# LIC_rack_OV-02.net
KiCad netlist of a schematic drawn in EAGLE
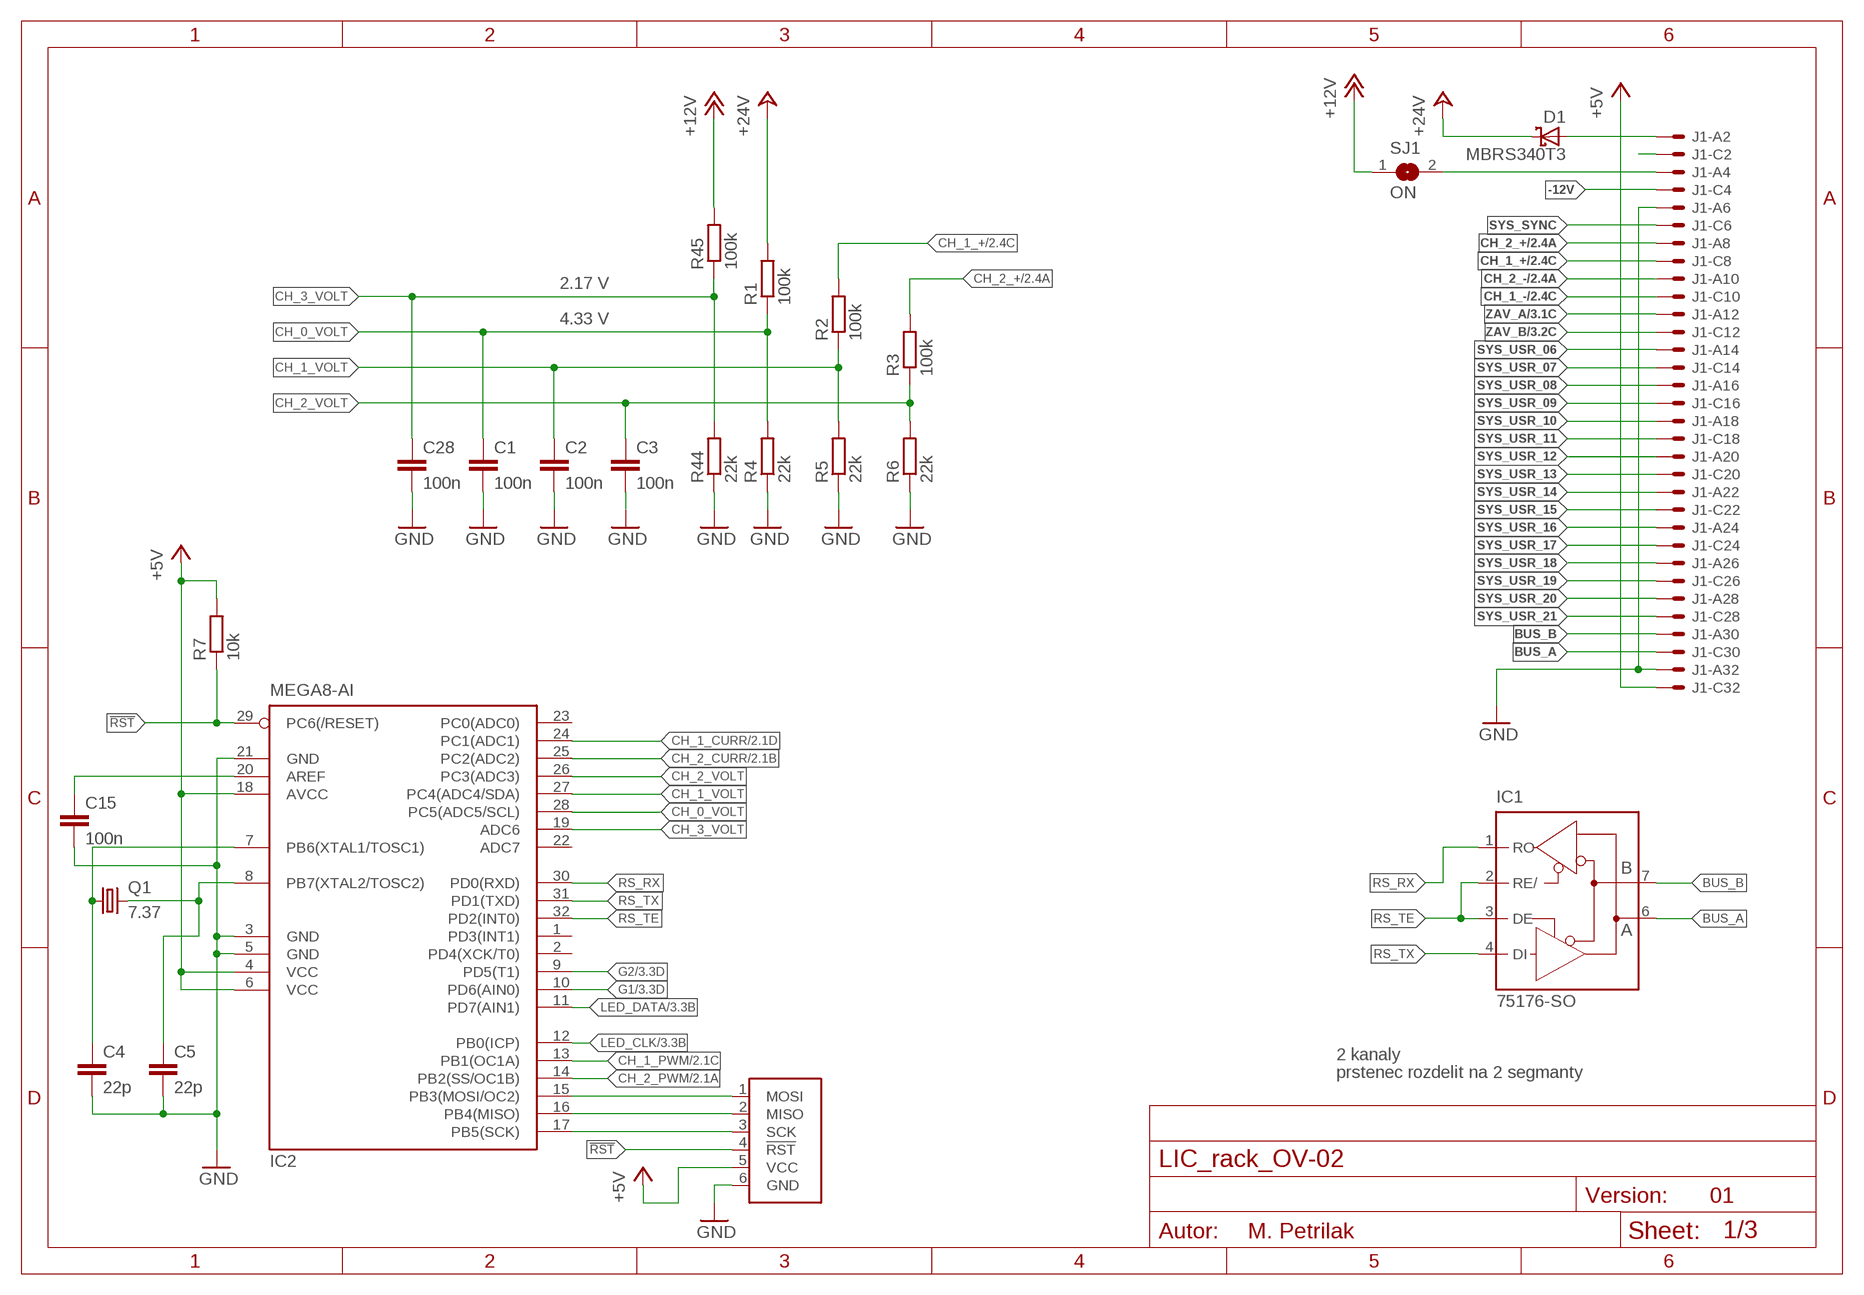
[diagram p0: schematic, sheet 1]
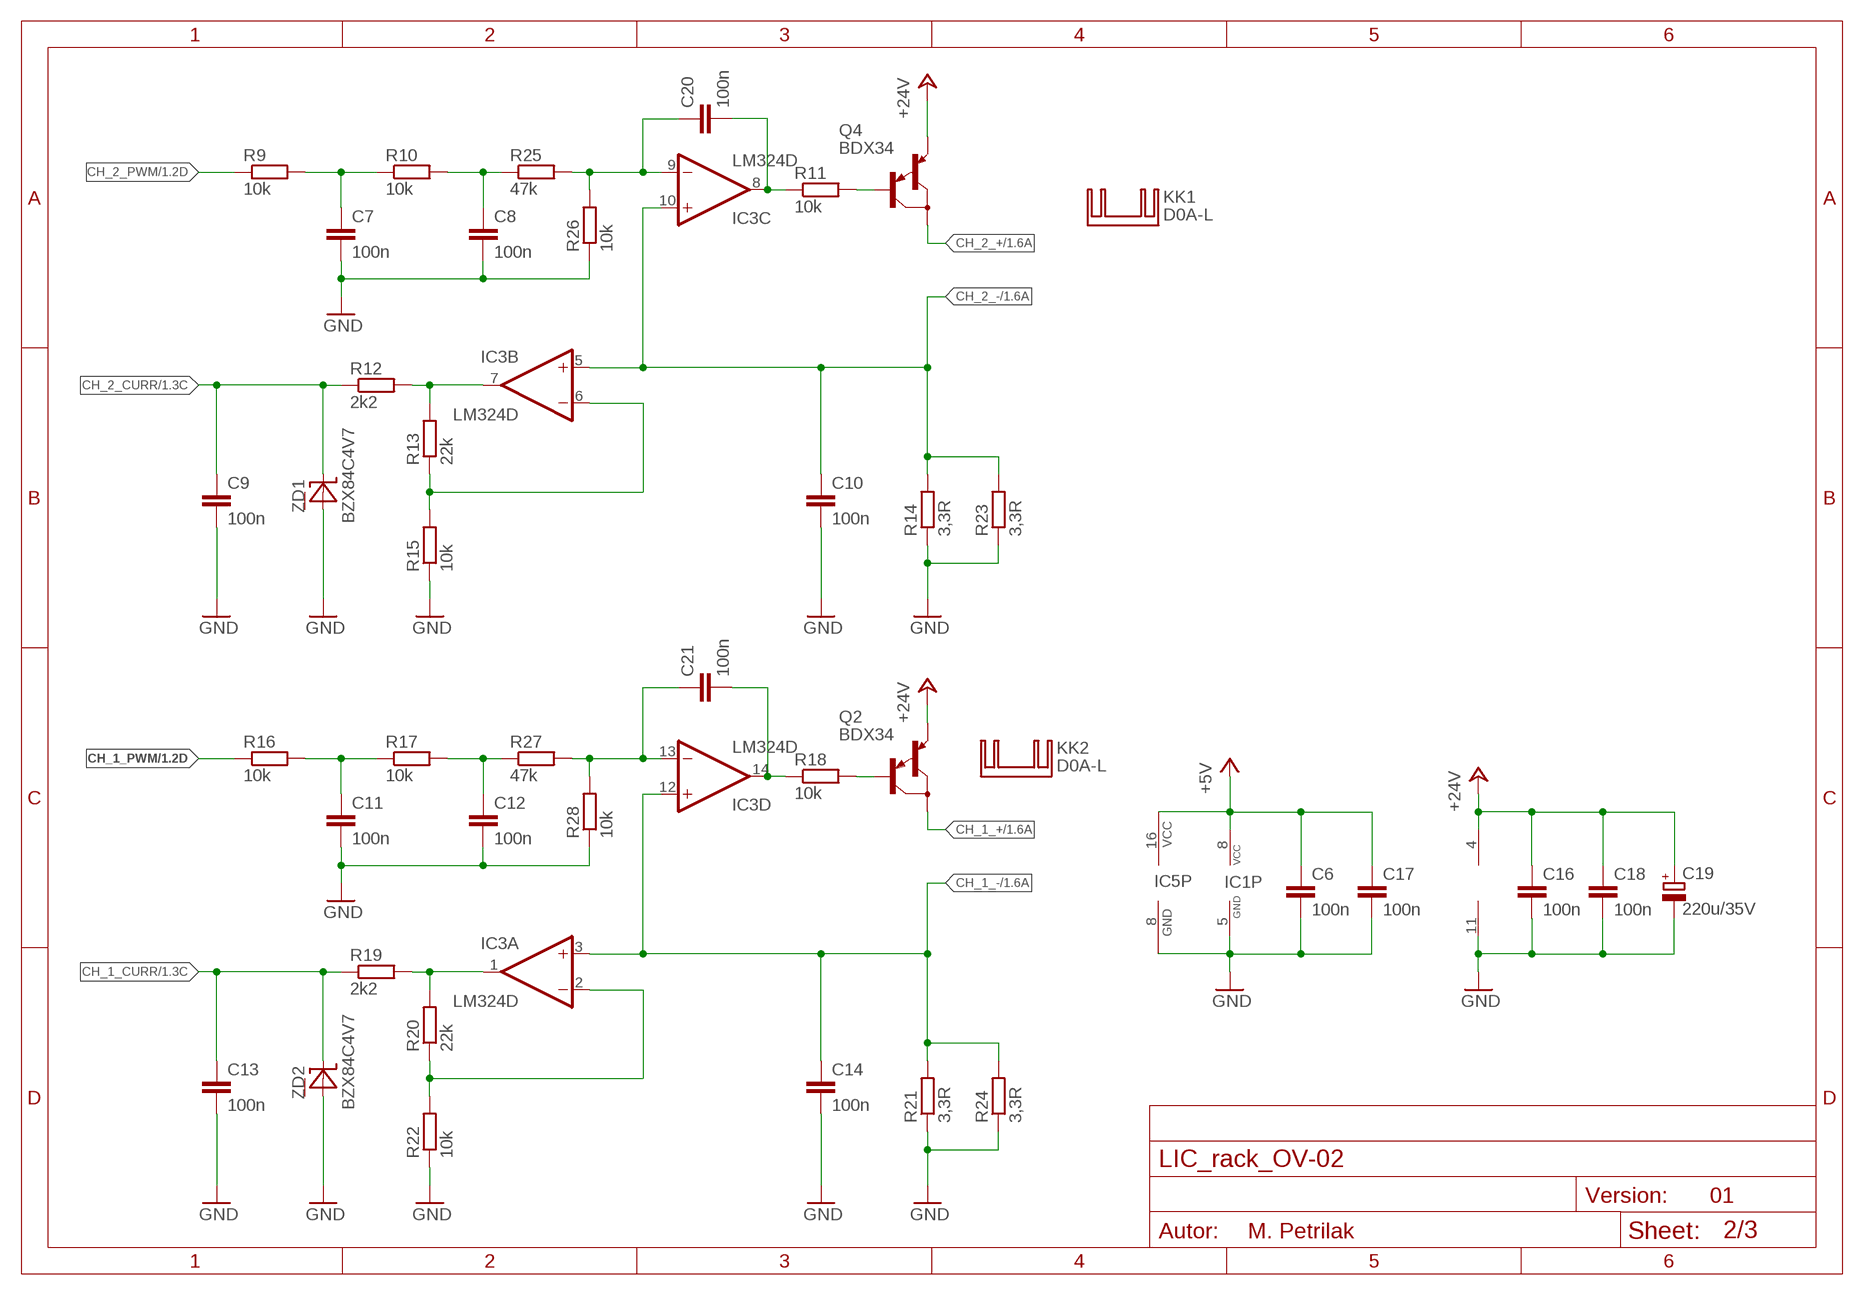
[diagram p1: schematic, sheet 2]
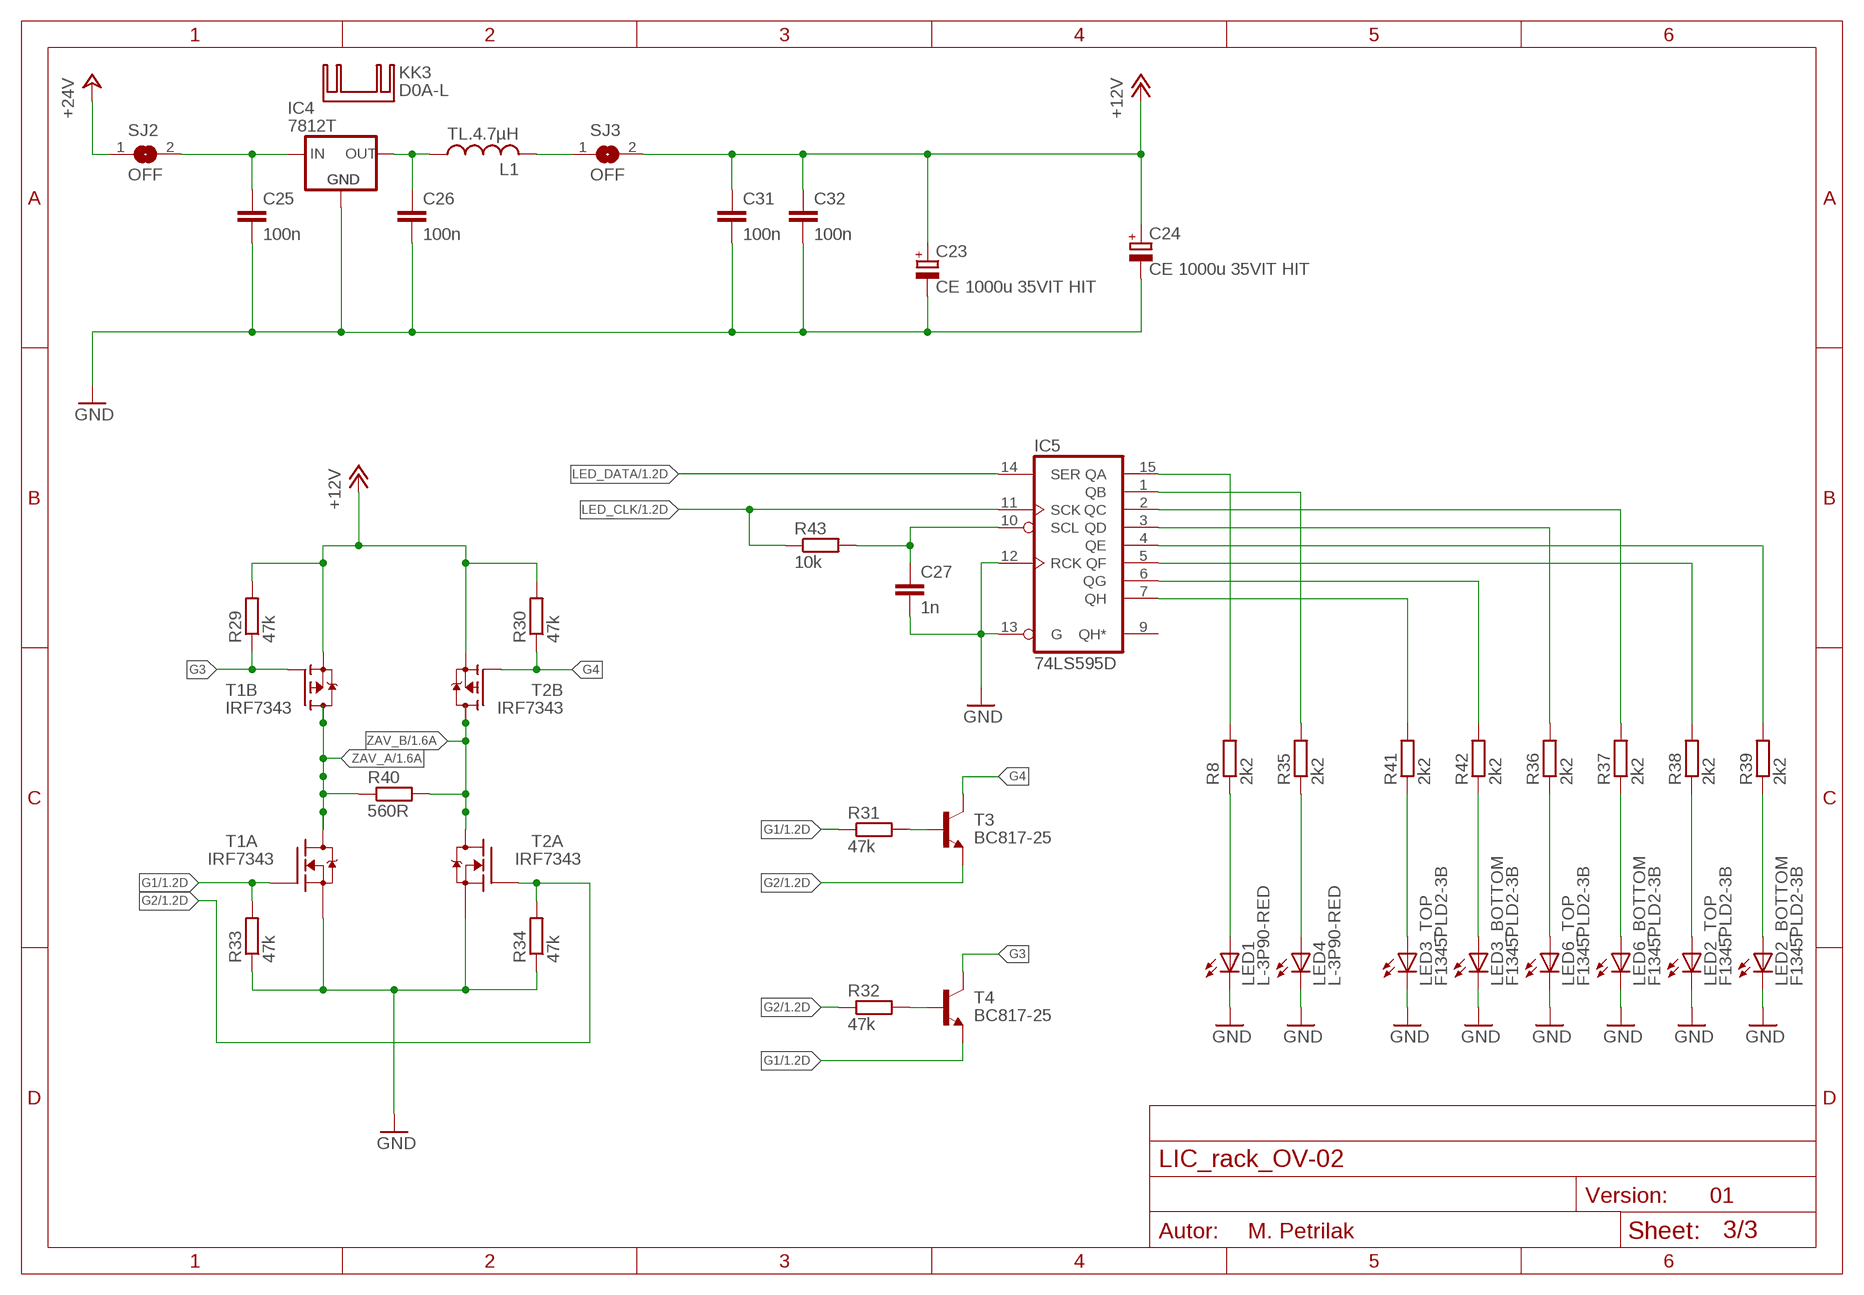
[diagram p2: schematic, sheet 3]

(export (version "E")
  (design (tool "Eeschema 10.0.6"))
  (components
    (comp (ref "C6")
      (value "100n")
      (footprint "eagle-import:C1206")
      (libsource (lib "eagle-import") (part "C-EUC1206"))
    )
    (comp (ref "C7")
      (value "100n")
      (footprint "eagle-import:C1206")
      (libsource (lib "eagle-import") (part "C-EUC1206"))
    )
    (comp (ref "C8")
      (value "100n")
      (footprint "eagle-import:C1206")
      (libsource (lib "eagle-import") (part "C-EUC1206"))
    )
    (comp (ref "C9")
      (value "100n")
      (footprint "eagle-import:C1206")
      (libsource (lib "eagle-import") (part "C-EUC1206"))
    )
    (comp (ref "C10")
      (value "100n")
      (footprint "eagle-import:C1206")
      (libsource (lib "eagle-import") (part "C-EUC1206"))
    )
    (comp (ref "C11")
      (value "100n")
      (footprint "eagle-import:C1206")
      (libsource (lib "eagle-import") (part "C-EUC1206"))
    )
    (comp (ref "C12")
      (value "100n")
      (footprint "eagle-import:C1206")
      (libsource (lib "eagle-import") (part "C-EUC1206"))
    )
    (comp (ref "C13")
      (value "100n")
      (footprint "eagle-import:C1206")
      (libsource (lib "eagle-import") (part "C-EUC1206"))
    )
    (comp (ref "C14")
      (value "100n")
      (footprint "eagle-import:C1206")
      (libsource (lib "eagle-import") (part "C-EUC1206"))
    )
    (comp (ref "C16")
      (value "100n")
      (footprint "eagle-import:C1206")
      (libsource (lib "eagle-import") (part "C-EUC1206"))
    )
    (comp (ref "C17")
      (value "100n")
      (footprint "eagle-import:C1206")
      (libsource (lib "eagle-import") (part "C-EUC1206"))
    )
    (comp (ref "C18")
      (value "100n")
      (footprint "eagle-import:C1206")
      (libsource (lib "eagle-import") (part "C-EUC1206"))
    )
    (comp (ref "C19")
      (value "220u/35V")
      (footprint "eagle-import:E3,5-8LR")
      (libsource (lib "eagle-import") (part "CPOL-EUE3.5-8LR"))
    )
    (comp (ref "C20")
      (value "100n")
      (footprint "eagle-import:C1206")
      (libsource (lib "eagle-import") (part "C-EUC1206"))
    )
    (comp (ref "C21")
      (value "100n")
      (footprint "eagle-import:C1206")
      (libsource (lib "eagle-import") (part "C-EUC1206"))
    )
    (comp (ref "IC1")
      (value "75176-SO")
      (footprint "eagle-import:SO08")
      (libsource (lib "eagle-import") (part "75176-SO"))
    )
    (comp (ref "IC3")
      (value "LM324D")
      (footprint "eagle-import:SO14")
      (libsource (lib "eagle-import") (part "LM324D"))
    )
    (comp (ref "IC5")
      (value "74LS595D")
      (footprint "eagle-import:SO16")
      (libsource (lib "eagle-import") (part "74595DLS"))
    )
    (comp (ref "KK1")
      (value "D0A-L")
      (footprint "eagle-import:D02A-L")
      (libsource (lib "eagle-import") (part "D0A-L"))
    )
    (comp (ref "KK2")
      (value "D0A-L")
      (footprint "eagle-import:D02A-L")
      (libsource (lib "eagle-import") (part "D0A-L"))
    )
    (comp (ref "Q2")
      (value "BDX34")
      (footprint "eagle-import:TO220")
      (libsource (lib "eagle-import") (part "BDX34"))
    )
    (comp (ref "Q4")
      (value "BDX34")
      (footprint "eagle-import:TO220")
      (libsource (lib "eagle-import") (part "BDX34"))
    )
    (comp (ref "R9")
      (value "10k")
      (footprint "eagle-import:R1206")
      (libsource (lib "eagle-import") (part "R-EU_R1206"))
    )
    (comp (ref "R10")
      (value "10k")
      (footprint "eagle-import:R1206")
      (libsource (lib "eagle-import") (part "R-EU_R1206"))
    )
    (comp (ref "R11")
      (value "10k")
      (footprint "eagle-import:R1206")
      (libsource (lib "eagle-import") (part "R-EU_R1206"))
    )
    (comp (ref "R12")
      (value "2k2")
      (footprint "eagle-import:R1206")
      (libsource (lib "eagle-import") (part "R-EU_R1206"))
    )
    (comp (ref "R13")
      (value "22k")
      (footprint "eagle-import:R1206")
      (libsource (lib "eagle-import") (part "R-EU_R1206"))
    )
    (comp (ref "R14")
      (value "3,3R")
      (footprint "eagle-import:0309_12")
      (libsource (lib "eagle-import") (part "R-EU_0309/12"))
    )
    (comp (ref "R15")
      (value "10k")
      (footprint "eagle-import:R1206")
      (libsource (lib "eagle-import") (part "R-EU_R1206"))
    )
    (comp (ref "R16")
      (value "10k")
      (footprint "eagle-import:R1206")
      (libsource (lib "eagle-import") (part "R-EU_R1206"))
    )
    (comp (ref "R17")
      (value "10k")
      (footprint "eagle-import:R1206")
      (libsource (lib "eagle-import") (part "R-EU_R1206"))
    )
    (comp (ref "R18")
      (value "10k")
      (footprint "eagle-import:R1206")
      (libsource (lib "eagle-import") (part "R-EU_R1206"))
    )
    (comp (ref "R19")
      (value "2k2")
      (footprint "eagle-import:R1206")
      (libsource (lib "eagle-import") (part "R-EU_R1206"))
    )
    (comp (ref "R20")
      (value "22k")
      (footprint "eagle-import:R1206")
      (libsource (lib "eagle-import") (part "R-EU_R1206"))
    )
    (comp (ref "R21")
      (value "3,3R")
      (footprint "eagle-import:0309_12")
      (libsource (lib "eagle-import") (part "R-EU_0309/12"))
    )
    (comp (ref "R22")
      (value "10k")
      (footprint "eagle-import:R1206")
      (libsource (lib "eagle-import") (part "R-EU_R1206"))
    )
    (comp (ref "R23")
      (value "3,3R")
      (footprint "eagle-import:R1206")
      (libsource (lib "eagle-import") (part "R-EU_R1206"))
    )
    (comp (ref "R24")
      (value "3,3R")
      (footprint "eagle-import:R1206")
      (libsource (lib "eagle-import") (part "R-EU_R1206"))
    )
    (comp (ref "R25")
      (value "47k")
      (footprint "eagle-import:R1206")
      (libsource (lib "eagle-import") (part "R-EU_R1206"))
    )
    (comp (ref "R26")
      (value "10k")
      (footprint "eagle-import:R1206")
      (libsource (lib "eagle-import") (part "R-EU_R1206"))
    )
    (comp (ref "R27")
      (value "47k")
      (footprint "eagle-import:R1206")
      (libsource (lib "eagle-import") (part "R-EU_R1206"))
    )
    (comp (ref "R28")
      (value "10k")
      (footprint "eagle-import:R1206")
      (libsource (lib "eagle-import") (part "R-EU_R1206"))
    )
    (comp (ref "ZD1")
      (value "BZX84C4V7")
      (footprint "eagle-import:SOT23")
      (libsource (lib "eagle-import") (part "BZX84C4V7"))
    )
    (comp (ref "ZD2")
      (value "BZX84C4V7")
      (footprint "eagle-import:SOT23")
      (libsource (lib "eagle-import") (part "BZX84C4V7"))
    )
    (comp (ref "C1")
      (value "100n")
      (footprint "eagle-import:C1206")
      (libsource (lib "eagle-import") (part "C-EUC1206"))
    )
    (comp (ref "C2")
      (value "100n")
      (footprint "eagle-import:C1206")
      (libsource (lib "eagle-import") (part "C-EUC1206"))
    )
    (comp (ref "C3")
      (value "100n")
      (footprint "eagle-import:C1206")
      (libsource (lib "eagle-import") (part "C-EUC1206"))
    )
    (comp (ref "C4")
      (value "22p")
      (footprint "eagle-import:C0805")
      (libsource (lib "eagle-import") (part "C-EUC0805"))
    )
    (comp (ref "C5")
      (value "22p")
      (footprint "eagle-import:C0805")
      (libsource (lib "eagle-import") (part "C-EUC0805"))
    )
    (comp (ref "C15")
      (value "100n")
      (footprint "eagle-import:C1206")
      (libsource (lib "eagle-import") (part "C-EUC1206"))
    )
    (comp (ref "C28")
      (value "100n")
      (footprint "eagle-import:C1206")
      (libsource (lib "eagle-import") (part "C-EUC1206"))
    )
    (comp (ref "D1")
      (value "MBRS340T3")
      (footprint "eagle-import:SMC")
      (libsource (lib "eagle-import") (part "MBRS340T3"))
    )
    (comp (ref "IC2")
      (value "MEGA8-AI")
      (footprint "eagle-import:TQFP32-08")
      (libsource (lib "eagle-import") (part "MEGA8-AI"))
    )
    (comp (ref "J1")
      (value "VG32SP")
      (footprint "eagle-import:VG32P")
      (libsource (lib "eagle-import") (part "VG32SP"))
    )
    (comp (ref "Q1")
      (value "7.37")
      (footprint "eagle-import:HC49U70")
      (libsource (lib "eagle-import") (part "XTAL"))
    )
    (comp (ref "R1")
      (value "100k")
      (footprint "eagle-import:R1206")
      (libsource (lib "eagle-import") (part "R-EU_R1206"))
    )
    (comp (ref "R2")
      (value "100k")
      (footprint "eagle-import:R1206")
      (libsource (lib "eagle-import") (part "R-EU_R1206"))
    )
    (comp (ref "R3")
      (value "100k")
      (footprint "eagle-import:R1206")
      (libsource (lib "eagle-import") (part "R-EU_R1206"))
    )
    (comp (ref "R4")
      (value "22k")
      (footprint "eagle-import:R1206")
      (libsource (lib "eagle-import") (part "R-EU_R1206"))
    )
    (comp (ref "R5")
      (value "22k")
      (footprint "eagle-import:R1206")
      (libsource (lib "eagle-import") (part "R-EU_R1206"))
    )
    (comp (ref "R6")
      (value "22k")
      (footprint "eagle-import:R1206")
      (libsource (lib "eagle-import") (part "R-EU_R1206"))
    )
    (comp (ref "R7")
      (value "10k")
      (footprint "eagle-import:R1206")
      (libsource (lib "eagle-import") (part "R-EU_R1206"))
    )
    (comp (ref "R44")
      (value "22k")
      (footprint "eagle-import:R1206")
      (libsource (lib "eagle-import") (part "R-EU_R1206"))
    )
    (comp (ref "R45")
      (value "100k")
      (footprint "eagle-import:R1206")
      (libsource (lib "eagle-import") (part "R-EU_R1206"))
    )
    (comp (ref "SJ1")
      (value "ON")
      (footprint "eagle-import:SJ-D")
      (libsource (lib "eagle-import") (part "SJ-DEFAULT"))
    )
    (comp (ref "U1")
      (value "ATPROG-V")
      (footprint "eagle-import:6410-06")
      (libsource (lib "eagle-import") (part "ATPROG-V"))
    )
    (comp (ref "C23")
      (value "CE 1000u 35VIT HIT")
      (footprint "eagle-import:E5-13X26-LR")
      (libsource (lib "eagle-import") (part "CPOL-EUE5-13X26-LR"))
    )
    (comp (ref "C24")
      (value "CE 1000u 35VIT HIT")
      (footprint "eagle-import:E5-13X26-LR")
      (libsource (lib "eagle-import") (part "CPOL-EUE5-13X26-LR"))
    )
    (comp (ref "C25")
      (value "100n")
      (footprint "eagle-import:C1206")
      (libsource (lib "eagle-import") (part "C-EUC1206"))
    )
    (comp (ref "C26")
      (value "100n")
      (footprint "eagle-import:C1206")
      (libsource (lib "eagle-import") (part "C-EUC1206"))
    )
    (comp (ref "C27")
      (value "1n")
      (footprint "eagle-import:C1206")
      (libsource (lib "eagle-import") (part "C-EUC1206"))
    )
    (comp (ref "C31")
      (value "100n")
      (footprint "eagle-import:C1206")
      (libsource (lib "eagle-import") (part "C-EUC1206"))
    )
    (comp (ref "C32")
      (value "100n")
      (footprint "eagle-import:C1206")
      (libsource (lib "eagle-import") (part "C-EUC1206"))
    )
    (comp (ref "IC4")
      (value "7812T")
      (footprint "eagle-import:TO220H")
      (libsource (lib "eagle-import") (part "78T12"))
    )
    (comp (ref "KK3")
      (value "D0A-L")
      (footprint "eagle-import:D02A-L")
      (libsource (lib "eagle-import") (part "D0A-L"))
    )
    (comp (ref "L1")
      (value "TL.4.7µH")
      (footprint "eagle-import:0207_12")
      (libsource (lib "eagle-import") (part "L-EU0207/12"))
    )
    (comp (ref "LED1")
      (value "L-3P90-RED")
      (footprint "eagle-import:L-3P90")
      (libsource (lib "eagle-import") (part "L-3P90-RED"))
    )
    (comp (ref "LED2")
      (value "F1345PLD2-3B")
      (footprint "eagle-import:F1345PLD2-3B")
      (libsource (lib "eagle-import") (part "F1345PLD2-3B"))
    )
    (comp (ref "LED3")
      (value "F1345PLD2-3B")
      (footprint "eagle-import:F1345PLD2-3B")
      (libsource (lib "eagle-import") (part "F1345PLD2-3B"))
    )
    (comp (ref "LED4")
      (value "L-3P90-RED")
      (footprint "eagle-import:L-3P90")
      (libsource (lib "eagle-import") (part "L-3P90-RED"))
    )
    (comp (ref "LED6")
      (value "F1345PLD2-3B")
      (footprint "eagle-import:F1345PLD2-3B")
      (libsource (lib "eagle-import") (part "F1345PLD2-3B"))
    )
    (comp (ref "R8")
      (value "2k2")
      (footprint "eagle-import:R1206")
      (libsource (lib "eagle-import") (part "R-EU_R1206"))
    )
    (comp (ref "R29")
      (value "47k")
      (footprint "eagle-import:R1206")
      (libsource (lib "eagle-import") (part "R-EU_R1206"))
    )
    (comp (ref "R30")
      (value "47k")
      (footprint "eagle-import:R1206")
      (libsource (lib "eagle-import") (part "R-EU_R1206"))
    )
    (comp (ref "R31")
      (value "47k")
      (footprint "eagle-import:R1206")
      (libsource (lib "eagle-import") (part "R-EU_R1206"))
    )
    (comp (ref "R32")
      (value "47k")
      (footprint "eagle-import:R1206")
      (libsource (lib "eagle-import") (part "R-EU_R1206"))
    )
    (comp (ref "R33")
      (value "47k")
      (footprint "eagle-import:R1206")
      (libsource (lib "eagle-import") (part "R-EU_R1206"))
    )
    (comp (ref "R34")
      (value "47k")
      (footprint "eagle-import:R1206")
      (libsource (lib "eagle-import") (part "R-EU_R1206"))
    )
    (comp (ref "R35")
      (value "2k2")
      (footprint "eagle-import:R1206")
      (libsource (lib "eagle-import") (part "R-EU_R1206"))
    )
    (comp (ref "R36")
      (value "2k2")
      (footprint "eagle-import:R1206")
      (libsource (lib "eagle-import") (part "R-EU_R1206"))
    )
    (comp (ref "R37")
      (value "2k2")
      (footprint "eagle-import:R1206")
      (libsource (lib "eagle-import") (part "R-EU_R1206"))
    )
    (comp (ref "R38")
      (value "2k2")
      (footprint "eagle-import:R1206")
      (libsource (lib "eagle-import") (part "R-EU_R1206"))
    )
    (comp (ref "R39")
      (value "2k2")
      (footprint "eagle-import:R1206")
      (libsource (lib "eagle-import") (part "R-EU_R1206"))
    )
    (comp (ref "R40")
      (value "560R")
      (footprint "eagle-import:R1206")
      (libsource (lib "eagle-import") (part "R-EU_R1206"))
    )
    (comp (ref "R41")
      (value "2k2")
      (footprint "eagle-import:R1206")
      (libsource (lib "eagle-import") (part "R-EU_R1206"))
    )
    (comp (ref "R42")
      (value "2k2")
      (footprint "eagle-import:R1206")
      (libsource (lib "eagle-import") (part "R-EU_R1206"))
    )
    (comp (ref "R43")
      (value "10k")
      (footprint "eagle-import:R1206")
      (libsource (lib "eagle-import") (part "R-EU_R1206"))
    )
    (comp (ref "SJ2")
      (value "OFF")
      (footprint "eagle-import:SJ")
      (libsource (lib "eagle-import") (part "SJ"))
    )
    (comp (ref "SJ3")
      (value "OFF")
      (footprint "eagle-import:SJ")
      (libsource (lib "eagle-import") (part "SJ"))
    )
    (comp (ref "T1")
      (value "IRF7343")
      (footprint "eagle-import:SO-8")
      (libsource (lib "eagle-import") (part "IRF7343"))
    )
    (comp (ref "T2")
      (value "IRF7343")
      (footprint "eagle-import:SO-8")
      (libsource (lib "eagle-import") (part "IRF7343"))
    )
    (comp (ref "T3")
      (value "BC817-25")
      (footprint "eagle-import:SOT23-BEC")
      (libsource (lib "eagle-import") (part "-NPN-SOT23-BECBC817-25"))
    )
    (comp (ref "T4")
      (value "BC817-25")
      (footprint "eagle-import:SOT23-BEC")
      (libsource (lib "eagle-import") (part "-NPN-SOT23-BECBC817-25"))
    )
  )
  (nets
    (net (code "1") (name "+5V") (class "Default")
      (node (ref "C17") (pin "1") (pinfunction "1_1") (pintype "passive"))
      (node (ref "C6") (pin "1") (pinfunction "1_1") (pintype "passive"))
      (node (ref "IC1") (pin "8") (pinfunction "VCC_8") (pintype "power_in"))
      (node (ref "IC2") (pin "18") (pinfunction "AVCC_18") (pintype "power_in"))
      (node (ref "IC2") (pin "4") (pinfunction "VCC_4") (pintype "power_in"))
      (node (ref "IC2") (pin "6") (pinfunction "VCC_6") (pintype "power_in"))
      (node (ref "IC5") (pin "16") (pinfunction "VCC_16") (pintype "power_in"))
      (node (ref "J1") (pin "C32") (pinfunction "MSV_C32") (pintype "passive"))
      (node (ref "R7") (pin "2") (pinfunction "2_2") (pintype "passive"))
      (node (ref "U1") (pin "5") (pinfunction "VCC_5") (pintype "power_in"))
    )
    (net (code "2") (name "+12V") (class "Default")
      (node (ref "C23") (pin "+") (pinfunction "+_+") (pintype "passive"))
      (node (ref "C24") (pin "+") (pinfunction "+_+") (pintype "passive"))
      (node (ref "C31") (pin "1") (pinfunction "1_1") (pintype "passive"))
      (node (ref "C32") (pin "1") (pinfunction "1_1") (pintype "passive"))
      (node (ref "R29") (pin "2") (pinfunction "2_2") (pintype "passive"))
      (node (ref "R30") (pin "2") (pinfunction "2_2") (pintype "passive"))
      (node (ref "R45") (pin "2") (pinfunction "2_2") (pintype "passive"))
      (node (ref "SJ1") (pin "1") (pinfunction "1_1") (pintype "passive"))
      (node (ref "SJ3") (pin "2") (pinfunction "2_2") (pintype "passive"))
      (node (ref "T1") (pin "3") (pinfunction "S_3") (pintype "passive"))
      (node (ref "T2") (pin "3") (pinfunction "S_3") (pintype "passive"))
    )
    (net (code "3") (name "+24V") (class "Default")
      (node (ref "C16") (pin "1") (pinfunction "1_1") (pintype "passive"))
      (node (ref "C18") (pin "1") (pinfunction "1_1") (pintype "passive"))
      (node (ref "C19") (pin "+") (pinfunction "+_+") (pintype "passive"))
      (node (ref "D1") (pin "C") (pinfunction "C_C") (pintype "passive"))
      (node (ref "IC3") (pin "4") (pinfunction "V+_4") (pintype "power_in"))
      (node (ref "Q2") (pin "3") (pinfunction "E_3") (pintype "passive"))
      (node (ref "Q4") (pin "3") (pinfunction "E_3") (pintype "passive"))
      (node (ref "R1") (pin "2") (pinfunction "2_2") (pintype "passive"))
      (node (ref "SJ2") (pin "1") (pinfunction "1_1") (pintype "passive"))
    )
    (net (code "4") (name "-12V") (class "Default")
      (node (ref "J1") (pin "C4") (pinfunction "MS_C4") (pintype "passive"))
    )
    (net (code "5") (name "BUS_A") (class "Default")
      (node (ref "IC1") (pin "6") (pinfunction "A_6") (pintype "passive"))
      (node (ref "J1") (pin "C30") (pinfunction "MS_C30") (pintype "passive"))
    )
    (net (code "6") (name "BUS_B") (class "Default")
      (node (ref "IC1") (pin "7") (pinfunction "B_7") (pintype "passive"))
      (node (ref "J1") (pin "A30") (pinfunction "MS_A30") (pintype "passive"))
    )
    (net (code "7") (name "CH_0_VOLT") (class "Default")
      (node (ref "C1") (pin "1") (pinfunction "1_1") (pintype "passive"))
      (node (ref "IC2") (pin "28") (pinfunction "PC5(ADC5/SCL)_28") (pintype "bidirectional"))
      (node (ref "R1") (pin "1") (pinfunction "1_1") (pintype "passive"))
      (node (ref "R4") (pin "2") (pinfunction "2_2") (pintype "passive"))
    )
    (net (code "8") (name "CH_1_+") (class "Default")
      (node (ref "J1") (pin "C8") (pinfunction "MS_C8") (pintype "passive"))
      (node (ref "Q2") (pin "2") (pinfunction "C_2") (pintype "passive"))
      (node (ref "R2") (pin "2") (pinfunction "2_2") (pintype "passive"))
    )
    (net (code "9") (name "CH_1_-") (class "Default")
      (node (ref "C14") (pin "1") (pinfunction "1_1") (pintype "passive"))
      (node (ref "IC3") (pin "12") (pinfunction "+IN_12") (pintype "input"))
      (node (ref "IC3") (pin "3") (pinfunction "+IN_3") (pintype "input"))
      (node (ref "J1") (pin "C10") (pinfunction "MS_C10") (pintype "passive"))
      (node (ref "R21") (pin "2") (pinfunction "2_2") (pintype "passive"))
      (node (ref "R24") (pin "2") (pinfunction "2_2") (pintype "passive"))
    )
    (net (code "10") (name "CH_1_CURR") (class "Default")
      (node (ref "C13") (pin "1") (pinfunction "1_1") (pintype "passive"))
      (node (ref "IC2") (pin "24") (pinfunction "PC1(ADC1)_24") (pintype "bidirectional"))
      (node (ref "R19") (pin "1") (pinfunction "1_1") (pintype "passive"))
      (node (ref "ZD2") (pin "3") (pinfunction "C_3") (pintype "passive"))
    )
    (net (code "11") (name "CH_1_PWM") (class "Default")
      (node (ref "IC2") (pin "13") (pinfunction "PB1(OC1A)_13") (pintype "bidirectional"))
      (node (ref "R16") (pin "1") (pinfunction "1_1") (pintype "passive"))
    )
    (net (code "12") (name "CH_1_VOLT") (class "Default")
      (node (ref "C2") (pin "1") (pinfunction "1_1") (pintype "passive"))
      (node (ref "IC2") (pin "27") (pinfunction "PC4(ADC4/SDA)_27") (pintype "bidirectional"))
      (node (ref "R2") (pin "1") (pinfunction "1_1") (pintype "passive"))
      (node (ref "R5") (pin "2") (pinfunction "2_2") (pintype "passive"))
    )
    (net (code "13") (name "CH_2_+") (class "Default")
      (node (ref "J1") (pin "A8") (pinfunction "MS_A8") (pintype "passive"))
      (node (ref "Q4") (pin "2") (pinfunction "C_2") (pintype "passive"))
      (node (ref "R3") (pin "2") (pinfunction "2_2") (pintype "passive"))
    )
    (net (code "14") (name "CH_2_-") (class "Default")
      (node (ref "C10") (pin "1") (pinfunction "1_1") (pintype "passive"))
      (node (ref "IC3") (pin "10") (pinfunction "+IN_10") (pintype "input"))
      (node (ref "IC3") (pin "5") (pinfunction "+IN_5") (pintype "input"))
      (node (ref "J1") (pin "A10") (pinfunction "MS_A10") (pintype "passive"))
      (node (ref "R14") (pin "2") (pinfunction "2_2") (pintype "passive"))
      (node (ref "R23") (pin "2") (pinfunction "2_2") (pintype "passive"))
    )
    (net (code "15") (name "CH_2_CURR") (class "Default")
      (node (ref "C9") (pin "1") (pinfunction "1_1") (pintype "passive"))
      (node (ref "IC2") (pin "25") (pinfunction "PC2(ADC2)_25") (pintype "bidirectional"))
      (node (ref "R12") (pin "1") (pinfunction "1_1") (pintype "passive"))
      (node (ref "ZD1") (pin "3") (pinfunction "C_3") (pintype "passive"))
    )
    (net (code "16") (name "CH_2_PWM") (class "Default")
      (node (ref "IC2") (pin "14") (pinfunction "PB2(SS/OC1B)_14") (pintype "bidirectional"))
      (node (ref "R9") (pin "1") (pinfunction "1_1") (pintype "passive"))
    )
    (net (code "17") (name "CH_2_VOLT") (class "Default")
      (node (ref "C3") (pin "1") (pinfunction "1_1") (pintype "passive"))
      (node (ref "IC2") (pin "26") (pinfunction "PC3(ADC3)_26") (pintype "bidirectional"))
      (node (ref "R3") (pin "1") (pinfunction "1_1") (pintype "passive"))
      (node (ref "R6") (pin "2") (pinfunction "2_2") (pintype "passive"))
    )
    (net (code "18") (name "CH_3_VOLT") (class "Default")
      (node (ref "C28") (pin "1") (pinfunction "1_1") (pintype "passive"))
      (node (ref "IC2") (pin "19") (pinfunction "ADC6_19") (pintype "bidirectional"))
      (node (ref "R44") (pin "2") (pinfunction "2_2") (pintype "passive"))
      (node (ref "R45") (pin "1") (pinfunction "1_1") (pintype "passive"))
    )
    (net (code "19") (name "G1") (class "Default")
      (node (ref "IC2") (pin "10") (pinfunction "PD6(AIN0)_10") (pintype "bidirectional"))
      (node (ref "R31") (pin "1") (pinfunction "1_1") (pintype "passive"))
      (node (ref "R33") (pin "2") (pinfunction "2_2") (pintype "passive"))
      (node (ref "T1") (pin "2") (pinfunction "G_2") (pintype "passive"))
      (node (ref "T4") (pin "E") (pinfunction "E_E") (pintype "passive"))
    )
    (net (code "20") (name "G2") (class "Default")
      (node (ref "IC2") (pin "9") (pinfunction "PD5(T1)_9") (pintype "bidirectional"))
      (node (ref "R32") (pin "1") (pinfunction "1_1") (pintype "passive"))
      (node (ref "R34") (pin "2") (pinfunction "2_2") (pintype "passive"))
      (node (ref "T2") (pin "2") (pinfunction "G_2") (pintype "passive"))
      (node (ref "T3") (pin "E") (pinfunction "E_E") (pintype "passive"))
    )
    (net (code "21") (name "G3") (class "Default")
      (node (ref "R29") (pin "1") (pinfunction "1_1") (pintype "passive"))
      (node (ref "T1") (pin "4") (pinfunction "G_4") (pintype "passive"))
      (node (ref "T4") (pin "C") (pinfunction "C_C") (pintype "passive"))
    )
    (net (code "22") (name "G4") (class "Default")
      (node (ref "R30") (pin "1") (pinfunction "1_1") (pintype "passive"))
      (node (ref "T2") (pin "4") (pinfunction "G_4") (pintype "passive"))
      (node (ref "T3") (pin "C") (pinfunction "C_C") (pintype "passive"))
    )
    (net (code "23") (name "GND") (class "Default")
      (node (ref "C1") (pin "2") (pinfunction "2_2") (pintype "passive"))
      (node (ref "C10") (pin "2") (pinfunction "2_2") (pintype "passive"))
      (node (ref "C11") (pin "2") (pinfunction "2_2") (pintype "passive"))
      (node (ref "C12") (pin "2") (pinfunction "2_2") (pintype "passive"))
      (node (ref "C13") (pin "2") (pinfunction "2_2") (pintype "passive"))
      (node (ref "C14") (pin "2") (pinfunction "2_2") (pintype "passive"))
      (node (ref "C15") (pin "2") (pinfunction "2_2") (pintype "passive"))
      (node (ref "C16") (pin "2") (pinfunction "2_2") (pintype "passive"))
      (node (ref "C17") (pin "2") (pinfunction "2_2") (pintype "passive"))
      (node (ref "C18") (pin "2") (pinfunction "2_2") (pintype "passive"))
      (node (ref "C19") (pin "-") (pinfunction "-_-") (pintype "passive"))
      (node (ref "C2") (pin "2") (pinfunction "2_2") (pintype "passive"))
      (node (ref "C23") (pin "-") (pinfunction "-_-") (pintype "passive"))
      (node (ref "C24") (pin "-") (pinfunction "-_-") (pintype "passive"))
      (node (ref "C25") (pin "2") (pinfunction "2_2") (pintype "passive"))
      (node (ref "C26") (pin "2") (pinfunction "2_2") (pintype "passive"))
      (node (ref "C27") (pin "2") (pinfunction "2_2") (pintype "passive"))
      (node (ref "C28") (pin "2") (pinfunction "2_2") (pintype "passive"))
      (node (ref "C3") (pin "2") (pinfunction "2_2") (pintype "passive"))
      (node (ref "C31") (pin "2") (pinfunction "2_2") (pintype "passive"))
      (node (ref "C32") (pin "2") (pinfunction "2_2") (pintype "passive"))
      (node (ref "C4") (pin "2") (pinfunction "2_2") (pintype "passive"))
      (node (ref "C5") (pin "2") (pinfunction "2_2") (pintype "passive"))
      (node (ref "C6") (pin "2") (pinfunction "2_2") (pintype "passive"))
      (node (ref "C7") (pin "2") (pinfunction "2_2") (pintype "passive"))
      (node (ref "C8") (pin "2") (pinfunction "2_2") (pintype "passive"))
      (node (ref "C9") (pin "2") (pinfunction "2_2") (pintype "passive"))
      (node (ref "IC1") (pin "5") (pinfunction "GND_5") (pintype "power_in"))
      (node (ref "IC2") (pin "21") (pinfunction "GND_21") (pintype "power_in"))
      (node (ref "IC2") (pin "3") (pinfunction "GND_3") (pintype "power_in"))
      (node (ref "IC2") (pin "5") (pinfunction "GND_5") (pintype "power_in"))
      (node (ref "IC3") (pin "11") (pinfunction "V-_11") (pintype "power_in"))
      (node (ref "IC4") (pin "2") (pinfunction "GND_2") (pintype "passive"))
      (node (ref "IC5") (pin "12") (pinfunction "RCK_12") (pintype "input"))
      (node (ref "IC5") (pin "13") (pinfunction "G_13") (pintype "input"))
      (node (ref "IC5") (pin "8") (pinfunction "GND_8") (pintype "power_in"))
      (node (ref "J1") (pin "A32") (pinfunction "MS_A32") (pintype "passive"))
      (node (ref "J1") (pin "A6") (pinfunction "MS_A6") (pintype "passive"))
      (node (ref "LED1") (pin "K") (pinfunction "C_K") (pintype "passive"))
      (node (ref "LED2") (pin "1K") (pinfunction "C_1K") (pintype "passive"))
      (node (ref "LED2") (pin "2K") (pinfunction "C_2K") (pintype "passive"))
      (node (ref "LED3") (pin "1K") (pinfunction "C_1K") (pintype "passive"))
      (node (ref "LED3") (pin "2K") (pinfunction "C_2K") (pintype "passive"))
      (node (ref "LED4") (pin "K") (pinfunction "C_K") (pintype "passive"))
      (node (ref "LED6") (pin "1K") (pinfunction "C_1K") (pintype "passive"))
      (node (ref "LED6") (pin "2K") (pinfunction "C_2K") (pintype "passive"))
      (node (ref "R14") (pin "1") (pinfunction "1_1") (pintype "passive"))
      (node (ref "R15") (pin "1") (pinfunction "1_1") (pintype "passive"))
      (node (ref "R21") (pin "1") (pinfunction "1_1") (pintype "passive"))
      (node (ref "R22") (pin "1") (pinfunction "1_1") (pintype "passive"))
      (node (ref "R23") (pin "1") (pinfunction "1_1") (pintype "passive"))
      (node (ref "R24") (pin "1") (pinfunction "1_1") (pintype "passive"))
      (node (ref "R26") (pin "1") (pinfunction "1_1") (pintype "passive"))
      (node (ref "R28") (pin "1") (pinfunction "1_1") (pintype "passive"))
      (node (ref "R33") (pin "1") (pinfunction "1_1") (pintype "passive"))
      (node (ref "R34") (pin "1") (pinfunction "1_1") (pintype "passive"))
      (node (ref "R4") (pin "1") (pinfunction "1_1") (pintype "passive"))
      (node (ref "R44") (pin "1") (pinfunction "1_1") (pintype "passive"))
      (node (ref "R5") (pin "1") (pinfunction "1_1") (pintype "passive"))
      (node (ref "R6") (pin "1") (pinfunction "1_1") (pintype "passive"))
      (node (ref "T1") (pin "1") (pinfunction "S_1") (pintype "passive"))
      (node (ref "T2") (pin "1") (pinfunction "S_1") (pintype "passive"))
      (node (ref "U1") (pin "6") (pinfunction "GND_6") (pintype "power_in"))
      (node (ref "ZD1") (pin "1") (pinfunction "A_1") (pintype "passive"))
      (node (ref "ZD2") (pin "1") (pinfunction "A_1") (pintype "passive"))
    )
    (net (code "24") (name "LED_CLK") (class "Default")
      (node (ref "IC2") (pin "12") (pinfunction "PB0(ICP)_12") (pintype "bidirectional"))
      (node (ref "IC5") (pin "11") (pinfunction "SCK_11") (pintype "input"))
      (node (ref "R43") (pin "1") (pinfunction "1_1") (pintype "passive"))
    )
    (net (code "25") (name "LED_DATA") (class "Default")
      (node (ref "IC2") (pin "11") (pinfunction "PD7(AIN1)_11") (pintype "bidirectional"))
      (node (ref "IC5") (pin "14") (pinfunction "SER_14") (pintype "input"))
    )
    (net (code "26") (name "Net-(C7-Pad1)") (class "Default")
      (node (ref "C7") (pin "1") (pinfunction "1_1") (pintype "passive"))
      (node (ref "R10") (pin "1") (pinfunction "1_1") (pintype "passive"))
      (node (ref "R9") (pin "2") (pinfunction "2_2") (pintype "passive"))
    )
    (net (code "27") (name "Net-(C8-Pad1)") (class "Default")
      (node (ref "C8") (pin "1") (pinfunction "1_1") (pintype "passive"))
      (node (ref "R10") (pin "2") (pinfunction "2_2") (pintype "passive"))
      (node (ref "R25") (pin "1") (pinfunction "1_1") (pintype "passive"))
    )
    (net (code "28") (name "Net-(C11-Pad1)") (class "Default")
      (node (ref "C11") (pin "1") (pinfunction "1_1") (pintype "passive"))
      (node (ref "R16") (pin "2") (pinfunction "2_2") (pintype "passive"))
      (node (ref "R17") (pin "1") (pinfunction "1_1") (pintype "passive"))
    )
    (net (code "29") (name "Net-(C12-Pad1)") (class "Default")
      (node (ref "C12") (pin "1") (pinfunction "1_1") (pintype "passive"))
      (node (ref "R17") (pin "2") (pinfunction "2_2") (pintype "passive"))
      (node (ref "R27") (pin "1") (pinfunction "1_1") (pintype "passive"))
    )
    (net (code "30") (name "Net-(IC2-AREF)") (class "Default")
      (node (ref "C15") (pin "1") (pinfunction "1_1") (pintype "passive"))
      (node (ref "IC2") (pin "20") (pinfunction "AREF_20") (pintype "passive"))
    )
    (net (code "31") (name "Net-(IC2-PB3(MOSI{slash}OC2))") (class "Default")
      (node (ref "IC2") (pin "15") (pinfunction "PB3(MOSI/OC2)_15") (pintype "bidirectional"))
      (node (ref "U1") (pin "1") (pinfunction "MOSI_1") (pintype "output"))
    )
    (net (code "32") (name "Net-(IC2-PB4(MISO))") (class "Default")
      (node (ref "IC2") (pin "16") (pinfunction "PB4(MISO)_16") (pintype "bidirectional"))
      (node (ref "U1") (pin "2") (pinfunction "MISO_2") (pintype "input"))
    )
    (net (code "33") (name "Net-(IC2-PB5(SCK))") (class "Default")
      (node (ref "IC2") (pin "17") (pinfunction "PB5(SCK)_17") (pintype "bidirectional"))
      (node (ref "U1") (pin "3") (pinfunction "SCK_3") (pintype "input"))
    )
    (net (code "34") (name "Net-(IC2-PB6(XTAL1{slash}TOSC1))") (class "Default")
      (node (ref "C4") (pin "1") (pinfunction "1_1") (pintype "passive"))
      (node (ref "IC2") (pin "7") (pinfunction "PB6(XTAL1/TOSC1)_7") (pintype "bidirectional"))
      (node (ref "Q1") (pin "1") (pinfunction "1_1") (pintype "passive"))
    )
    (net (code "35") (name "Net-(IC2-PB7(XTAL2{slash}TOSC2))") (class "Default")
      (node (ref "C5") (pin "1") (pinfunction "1_1") (pintype "passive"))
      (node (ref "IC2") (pin "8") (pinfunction "PB7(XTAL2/TOSC2)_8") (pintype "bidirectional"))
      (node (ref "Q1") (pin "2") (pinfunction "2_2") (pintype "passive"))
    )
    (net (code "36") (name "Net-(IC3A--IN)") (class "Default")
      (node (ref "IC3") (pin "2") (pinfunction "-IN_2") (pintype "input"))
      (node (ref "R20") (pin "1") (pinfunction "1_1") (pintype "passive"))
      (node (ref "R22") (pin "2") (pinfunction "2_2") (pintype "passive"))
    )
    (net (code "37") (name "Net-(IC3A-OUT)") (class "Default")
      (node (ref "IC3") (pin "1") (pinfunction "OUT_1") (pintype "output"))
      (node (ref "R19") (pin "2") (pinfunction "2_2") (pintype "passive"))
      (node (ref "R20") (pin "2") (pinfunction "2_2") (pintype "passive"))
    )
    (net (code "38") (name "Net-(IC3B--IN)") (class "Default")
      (node (ref "IC3") (pin "6") (pinfunction "-IN_6") (pintype "input"))
      (node (ref "R13") (pin "1") (pinfunction "1_1") (pintype "passive"))
      (node (ref "R15") (pin "2") (pinfunction "2_2") (pintype "passive"))
    )
    (net (code "39") (name "Net-(IC3B-OUT)") (class "Default")
      (node (ref "IC3") (pin "7") (pinfunction "OUT_7") (pintype "output"))
      (node (ref "R12") (pin "2") (pinfunction "2_2") (pintype "passive"))
      (node (ref "R13") (pin "2") (pinfunction "2_2") (pintype "passive"))
    )
    (net (code "40") (name "Net-(IC3C--IN)") (class "Default")
      (node (ref "C20") (pin "1") (pinfunction "1_1") (pintype "passive"))
      (node (ref "IC3") (pin "9") (pinfunction "-IN_9") (pintype "input"))
      (node (ref "R25") (pin "2") (pinfunction "2_2") (pintype "passive"))
      (node (ref "R26") (pin "2") (pinfunction "2_2") (pintype "passive"))
    )
    (net (code "41") (name "Net-(IC3C-OUT)") (class "Default")
      (node (ref "C20") (pin "2") (pinfunction "2_2") (pintype "passive"))
      (node (ref "IC3") (pin "8") (pinfunction "OUT_8") (pintype "output"))
      (node (ref "R11") (pin "1") (pinfunction "1_1") (pintype "passive"))
    )
    (net (code "42") (name "Net-(IC3D--IN)") (class "Default")
      (node (ref "C21") (pin "1") (pinfunction "1_1") (pintype "passive"))
      (node (ref "IC3") (pin "13") (pinfunction "-IN_13") (pintype "input"))
      (node (ref "R27") (pin "2") (pinfunction "2_2") (pintype "passive"))
      (node (ref "R28") (pin "2") (pinfunction "2_2") (pintype "passive"))
    )
    (net (code "43") (name "Net-(IC3D-OUT)") (class "Default")
      (node (ref "C21") (pin "2") (pinfunction "2_2") (pintype "passive"))
      (node (ref "IC3") (pin "14") (pinfunction "OUT_14") (pintype "output"))
      (node (ref "R18") (pin "1") (pinfunction "1_1") (pintype "passive"))
    )
    (net (code "44") (name "Net-(IC4-VI)") (class "Default")
      (node (ref "C25") (pin "1") (pinfunction "1_1") (pintype "passive"))
      (node (ref "IC4") (pin "1") (pinfunction "VI_1") (pintype "input"))
      (node (ref "SJ2") (pin "2") (pinfunction "2_2") (pintype "passive"))
    )
    (net (code "45") (name "Net-(IC4-VO)") (class "Default")
      (node (ref "C26") (pin "1") (pinfunction "1_1") (pintype "passive"))
      (node (ref "IC4") (pin "3") (pinfunction "VO_3") (pintype "passive"))
      (node (ref "L1") (pin "1") (pinfunction "1_1") (pintype "passive"))
    )
    (net (code "46") (name "Net-(IC5A-QA)") (class "Default")
      (node (ref "IC5") (pin "15") (pinfunction "QA_15") (pintype "tri_state"))
      (node (ref "R8") (pin "2") (pinfunction "2_2") (pintype "passive"))
    )
    (net (code "47") (name "Net-(IC5A-QB)") (class "Default")
      (node (ref "IC5") (pin "1") (pinfunction "QB_1") (pintype "tri_state"))
      (node (ref "R35") (pin "2") (pinfunction "2_2") (pintype "passive"))
    )
    (net (code "48") (name "Net-(IC5A-QC)") (class "Default")
      (node (ref "IC5") (pin "2") (pinfunction "QC_2") (pintype "tri_state"))
      (node (ref "R37") (pin "2") (pinfunction "2_2") (pintype "passive"))
    )
    (net (code "49") (name "Net-(IC5A-QD)") (class "Default")
      (node (ref "IC5") (pin "3") (pinfunction "QD_3") (pintype "tri_state"))
      (node (ref "R36") (pin "2") (pinfunction "2_2") (pintype "passive"))
    )
    (net (code "50") (name "Net-(IC5A-QE)") (class "Default")
      (node (ref "IC5") (pin "4") (pinfunction "QE_4") (pintype "tri_state"))
      (node (ref "R39") (pin "2") (pinfunction "2_2") (pintype "passive"))
    )
    (net (code "51") (name "Net-(IC5A-QF)") (class "Default")
      (node (ref "IC5") (pin "5") (pinfunction "QF_5") (pintype "tri_state"))
      (node (ref "R38") (pin "2") (pinfunction "2_2") (pintype "passive"))
    )
    (net (code "52") (name "Net-(IC5A-QG)") (class "Default")
      (node (ref "IC5") (pin "6") (pinfunction "QG_6") (pintype "tri_state"))
      (node (ref "R42") (pin "2") (pinfunction "2_2") (pintype "passive"))
    )
    (net (code "53") (name "Net-(IC5A-QH)") (class "Default")
      (node (ref "IC5") (pin "7") (pinfunction "QH_7") (pintype "tri_state"))
      (node (ref "R41") (pin "2") (pinfunction "2_2") (pintype "passive"))
    )
    (net (code "54") (name "Net-(IC5A-SCL)") (class "Default")
      (node (ref "C27") (pin "1") (pinfunction "1_1") (pintype "passive"))
      (node (ref "IC5") (pin "10") (pinfunction "SCL_10") (pintype "input"))
      (node (ref "R43") (pin "2") (pinfunction "2_2") (pintype "passive"))
    )
    (net (code "55") (name "Net-(J1F-MS)") (class "Default")
      (node (ref "D1") (pin "A") (pinfunction "A_A") (pintype "passive"))
      (node (ref "J1") (pin "A2") (pinfunction "MS_A2") (pintype "passive"))
    )
    (net (code "56") (name "Net-(J1N-MS)") (class "Default")
      (node (ref "J1") (pin "A4") (pinfunction "MS_A4") (pintype "passive"))
      (node (ref "SJ1") (pin "2") (pinfunction "2_2") (pintype "passive"))
    )
    (net (code "57") (name "Net-(L1-Pad2)") (class "Default")
      (node (ref "L1") (pin "2") (pinfunction "2_2") (pintype "passive"))
      (node (ref "SJ3") (pin "1") (pinfunction "1_1") (pintype "passive"))
    )
    (net (code "58") (name "Net-(LED1-PadA)") (class "Default")
      (node (ref "LED1") (pin "A") (pinfunction "A_A") (pintype "passive"))
      (node (ref "R8") (pin "1") (pinfunction "1_1") (pintype "passive"))
    )
    (net (code "59") (name "Net-(LED2A-A)") (class "Default")
      (node (ref "LED2") (pin "1A") (pinfunction "A_1A") (pintype "passive"))
      (node (ref "R39") (pin "1") (pinfunction "1_1") (pintype "passive"))
    )
    (net (code "60") (name "Net-(LED2B-A)") (class "Default")
      (node (ref "LED2") (pin "2A") (pinfunction "A_2A") (pintype "passive"))
      (node (ref "R38") (pin "1") (pinfunction "1_1") (pintype "passive"))
    )
    (net (code "61") (name "Net-(LED3A-A)") (class "Default")
      (node (ref "LED3") (pin "1A") (pinfunction "A_1A") (pintype "passive"))
      (node (ref "R42") (pin "1") (pinfunction "1_1") (pintype "passive"))
    )
    (net (code "62") (name "Net-(LED3B-A)") (class "Default")
      (node (ref "LED3") (pin "2A") (pinfunction "A_2A") (pintype "passive"))
      (node (ref "R41") (pin "1") (pinfunction "1_1") (pintype "passive"))
    )
    (net (code "63") (name "Net-(LED4-PadA)") (class "Default")
      (node (ref "LED4") (pin "A") (pinfunction "A_A") (pintype "passive"))
      (node (ref "R35") (pin "1") (pinfunction "1_1") (pintype "passive"))
    )
    (net (code "64") (name "Net-(LED6A-A)") (class "Default")
      (node (ref "LED6") (pin "1A") (pinfunction "A_1A") (pintype "passive"))
      (node (ref "R37") (pin "1") (pinfunction "1_1") (pintype "passive"))
    )
    (net (code "65") (name "Net-(LED6B-A)") (class "Default")
      (node (ref "LED6") (pin "2A") (pinfunction "A_2A") (pintype "passive"))
      (node (ref "R36") (pin "1") (pinfunction "1_1") (pintype "passive"))
    )
    (net (code "66") (name "Net-(Q2-B)") (class "Default")
      (node (ref "Q2") (pin "1") (pinfunction "B_1") (pintype "passive"))
      (node (ref "R18") (pin "2") (pinfunction "2_2") (pintype "passive"))
    )
    (net (code "67") (name "Net-(Q4-B)") (class "Default")
      (node (ref "Q4") (pin "1") (pinfunction "B_1") (pintype "passive"))
      (node (ref "R11") (pin "2") (pinfunction "2_2") (pintype "passive"))
    )
    (net (code "68") (name "Net-(R31-Pad2)") (class "Default")
      (node (ref "R31") (pin "2") (pinfunction "2_2") (pintype "passive"))
      (node (ref "T3") (pin "B") (pinfunction "B_B") (pintype "passive"))
    )
    (net (code "69") (name "Net-(R32-Pad2)") (class "Default")
      (node (ref "R32") (pin "2") (pinfunction "2_2") (pintype "passive"))
      (node (ref "T4") (pin "B") (pinfunction "B_B") (pintype "passive"))
    )
    (net (code "70") (name "RS_RX") (class "Default")
      (node (ref "IC1") (pin "1") (pinfunction "RO_1") (pintype "output"))
      (node (ref "IC2") (pin "30") (pinfunction "PD0(RXD)_30") (pintype "bidirectional"))
    )
    (net (code "71") (name "RS_TE") (class "Default")
      (node (ref "IC1") (pin "2") (pinfunction "RE/_2") (pintype "input"))
      (node (ref "IC1") (pin "3") (pinfunction "DE_3") (pintype "input"))
      (node (ref "IC2") (pin "32") (pinfunction "PD2(INT0)_32") (pintype "bidirectional"))
    )
    (net (code "72") (name "RS_TX") (class "Default")
      (node (ref "IC1") (pin "4") (pinfunction "DI_4") (pintype "input"))
      (node (ref "IC2") (pin "31") (pinfunction "PD1(TXD)_31") (pintype "bidirectional"))
    )
    (net (code "73") (name "SYS_SYNC") (class "Default")
      (node (ref "J1") (pin "C6") (pinfunction "MS_C6") (pintype "passive"))
    )
    (net (code "74") (name "SYS_USR_06") (class "Default")
      (node (ref "J1") (pin "A14") (pinfunction "MS_A14") (pintype "passive"))
    )
    (net (code "75") (name "SYS_USR_07") (class "Default")
      (node (ref "J1") (pin "C14") (pinfunction "MS_C14") (pintype "passive"))
    )
    (net (code "76") (name "SYS_USR_08") (class "Default")
      (node (ref "J1") (pin "A16") (pinfunction "MS_A16") (pintype "passive"))
    )
    (net (code "77") (name "SYS_USR_09") (class "Default")
      (node (ref "J1") (pin "C16") (pinfunction "MS_C16") (pintype "passive"))
    )
    (net (code "78") (name "SYS_USR_10") (class "Default")
      (node (ref "J1") (pin "A18") (pinfunction "MS_A18") (pintype "passive"))
    )
    (net (code "79") (name "SYS_USR_11") (class "Default")
      (node (ref "J1") (pin "C18") (pinfunction "MS_C18") (pintype "passive"))
    )
    (net (code "80") (name "SYS_USR_12") (class "Default")
      (node (ref "J1") (pin "A20") (pinfunction "MS_A20") (pintype "passive"))
    )
    (net (code "81") (name "SYS_USR_13") (class "Default")
      (node (ref "J1") (pin "C20") (pinfunction "MS_C20") (pintype "passive"))
    )
    (net (code "82") (name "SYS_USR_14") (class "Default")
      (node (ref "J1") (pin "A22") (pinfunction "MS_A22") (pintype "passive"))
    )
    (net (code "83") (name "SYS_USR_15") (class "Default")
      (node (ref "J1") (pin "C22") (pinfunction "MS_C22") (pintype "passive"))
    )
    (net (code "84") (name "SYS_USR_16") (class "Default")
      (node (ref "J1") (pin "A24") (pinfunction "MS_A24") (pintype "passive"))
    )
    (net (code "85") (name "SYS_USR_17") (class "Default")
      (node (ref "J1") (pin "C24") (pinfunction "MS_C24") (pintype "passive"))
    )
    (net (code "86") (name "SYS_USR_18") (class "Default")
      (node (ref "J1") (pin "A26") (pinfunction "MS_A26") (pintype "passive"))
    )
    (net (code "87") (name "SYS_USR_19") (class "Default")
      (node (ref "J1") (pin "C26") (pinfunction "MS_C26") (pintype "passive"))
    )
    (net (code "88") (name "SYS_USR_20") (class "Default")
      (node (ref "J1") (pin "A28") (pinfunction "MS_A28") (pintype "passive"))
    )
    (net (code "89") (name "SYS_USR_21") (class "Default")
      (node (ref "J1") (pin "C28") (pinfunction "MS_C28") (pintype "passive"))
    )
    (net (code "90") (name "ZAV_A") (class "Default")
      (node (ref "J1") (pin "A12") (pinfunction "MS_A12") (pintype "passive"))
      (node (ref "R40") (pin "1") (pinfunction "1_1") (pintype "passive"))
      (node (ref "T1") (pin "5") (pinfunction "D_5") (pintype "passive"))
      (node (ref "T1") (pin "6") (pinfunction "D1_6") (pintype "passive"))
      (node (ref "T1") (pin "7") (pinfunction "D_7") (pintype "passive"))
      (node (ref "T1") (pin "8") (pinfunction "D1_8") (pintype "passive"))
    )
    (net (code "91") (name "ZAV_B") (class "Default")
      (node (ref "J1") (pin "C12") (pinfunction "MS_C12") (pintype "passive"))
      (node (ref "R40") (pin "2") (pinfunction "2_2") (pintype "passive"))
      (node (ref "T2") (pin "5") (pinfunction "D_5") (pintype "passive"))
      (node (ref "T2") (pin "6") (pinfunction "D1_6") (pintype "passive"))
      (node (ref "T2") (pin "7") (pinfunction "D_7") (pintype "passive"))
      (node (ref "T2") (pin "8") (pinfunction "D1_8") (pintype "passive"))
    )
    (net (code "92") (name "unconnected-(IC2-ADC7-Pad22)") (class "Default")
      (node (ref "IC2") (pin "22") (pinfunction "ADC7_22") (pintype "bidirectional"))
    )
    (net (code "93") (name "unconnected-(IC2-PC0(ADC0)-Pad23)") (class "Default")
      (node (ref "IC2") (pin "23") (pinfunction "PC0(ADC0)_23") (pintype "bidirectional"))
    )
    (net (code "94") (name "unconnected-(IC2-PD3(INT1)-Pad1)") (class "Default")
      (node (ref "IC2") (pin "1") (pinfunction "PD3(INT1)_1") (pintype "bidirectional"))
    )
    (net (code "95") (name "unconnected-(IC2-PD4(XCK{slash}T0)-Pad2)") (class "Default")
      (node (ref "IC2") (pin "2") (pinfunction "PD4(XCK/T0)_2") (pintype "bidirectional"))
    )
    (net (code "96") (name "unconnected-(IC5A-QH*-Pad9)") (class "Default")
      (node (ref "IC5") (pin "9") (pinfunction "QH*_9") (pintype "tri_state"))
    )
    (net (code "97") (name "unconnected-(J1V-MS-PadC2)") (class "Default")
      (node (ref "J1") (pin "C2") (pinfunction "MS_C2") (pintype "passive"))
    )
    (net (code "98") (name "unconnected-(ZD1-NC-Pad2)") (class "Default")
      (node (ref "ZD1") (pin "2") (pinfunction "NC_2") (pintype "passive"))
    )
    (net (code "99") (name "unconnected-(ZD2-NC-Pad2)") (class "Default")
      (node (ref "ZD2") (pin "2") (pinfunction "NC_2") (pintype "passive"))
    )
    (net (code "100") (name "~{RST}") (class "Default")
      (node (ref "IC2") (pin "29") (pinfunction "PC6(/RESET)_29") (pintype "bidirectional"))
      (node (ref "R7") (pin "1") (pinfunction "1_1") (pintype "passive"))
      (node (ref "U1") (pin "4") (pinfunction "~{RST}_4") (pintype "input"))
    )
  )
)
